# ISL91107.net
KiCad netlist of a schematic drawn in Altium Designer
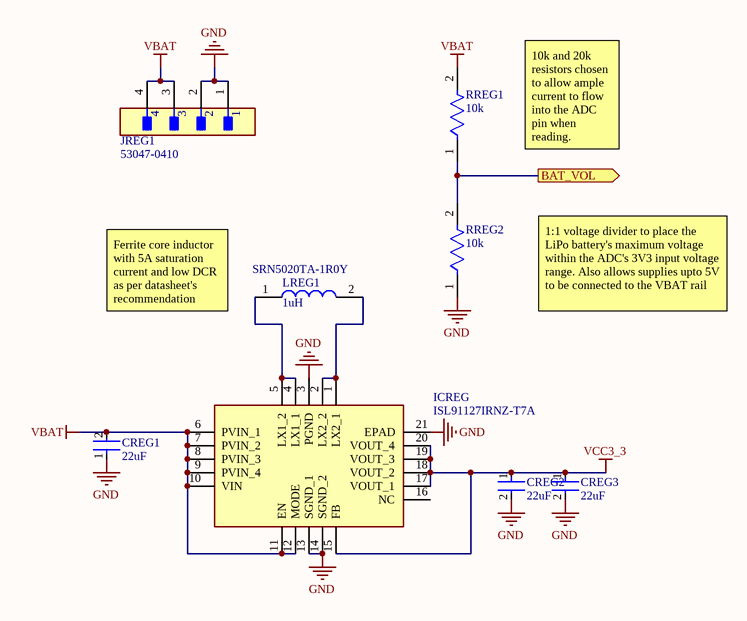
[diagram p0: ISL91107.SchDoc]

(export (version "E")
  (design (tool "Eeschema 10.0.6"))
  (components
    (comp (ref "CREG1")
      (value "22uF")
      (footprint "FP-GRM188-0_2-IPC_C")
      (description "Chip Multilayer Ceramic Capacitors for General Purpose, 0603, 22uF, X5R, 15%, 20%, 10V")
      (fields (field (name "TOLERANCE") "20%"))
      (libsource (lib "Altium Content Vault") (part "11868f565c42a9108669ba33697ecf6"))
    )
    (comp (ref "CREG2")
      (value "22uF")
      (footprint "FP-GRM188-0_2-IPC_C")
      (description "Chip Multilayer Ceramic Capacitors for General Purpose, 0603, 22uF, X5R, 15%, 20%, 10V")
      (fields (field (name "TOLERANCE") "20%"))
      (libsource (lib "Altium Content Vault") (part "11868f565c42a9108669ba33697ecf6"))
    )
    (comp (ref "CREG3")
      (value "22uF")
      (footprint "FP-GRM188-0_2-IPC_C")
      (description "Chip Multilayer Ceramic Capacitors for General Purpose, 0603, 22uF, X5R, 15%, 20%, 10V")
      (fields (field (name "TOLERANCE") "20%"))
      (libsource (lib "Altium Content Vault") (part "11868f565c42a9108669ba33697ecf6"))
    )
    (comp (ref "ICREG")
      (value "ISL91127IRNZ-T7A")
      (footprint "SamacSys:QFN50P400X400X100-21N")
      (description "Integrated Circuit")
      (fields (field (name "MOUSER PART NUMBER") "968-ISL91127IRNZ-T7A"))
      (libsource (lib "*") (part "ISL91127IRNZ-T7A"))
    )
    (comp (ref "JREG1")
      (value "53047-0410")
      (footprint "FP-53047-0410-MFG")
      (description "CONN HEADER VERT 4POS 1.25MM")
      (fields (field (name "VOLTAGE") "125V"))
      (libsource (lib "Altium Content Vault") (part "299a8cea1bdcbc3624fe62c390fa72c"))
    )
    (comp (ref "LREG1")
      (value "1uH")
      (footprint "SamacSys:INDC5050X200N")
      (description "Inductor")
      (fields
        (field (name "MANUFACTURER_PART_NUMBER") "SRN5020TA-1R0Y")
        (field (name "MOUSER PART NUMBER") "652-SRN5020TA-1R0Y")
        (field (name "SUPPLIER PART NUMBER 1") "SRN5020TA-1R0Y")
      )
      (libsource (lib "*") (part "SRN5020TA-1R0Y"))
    )
    (comp (ref "RREG1")
      (value "10k")
      (footprint "FP-ERJ3G-IPC_C")
      (description "RES SMD 10K OHM 5% 1/10W 0603")
      (fields (field (name "TOLERANCE") "5%"))
      (libsource (lib "Altium Content Vault") (part "1029c3af85768c4190bb7ad29bc67b5"))
    )
    (comp (ref "RREG2")
      (value "10k")
      (footprint "FP-ERJ3G-IPC_C")
      (description "RES SMD 10K OHM 5% 1/10W 0603")
      (fields (field (name "TOLERANCE") "5%"))
      (libsource (lib "Altium Content Vault") (part "1029c3af85768c4190bb7ad29bc67b5"))
    )
  )
  (nets
    (net (code "1") (name "/BAT_VOL") (class "Default")
      (node (ref "RREG1") (pin "1") (pinfunction "1_1") (pintype "passive"))
      (node (ref "RREG2") (pin "2") (pinfunction "2_2") (pintype "passive"))
    )
    (net (code "2") (name "GND") (class "Default")
      (node (ref "CREG1") (pin "1") (pinfunction "1_1") (pintype "passive"))
      (node (ref "CREG2") (pin "2") (pinfunction "2_2") (pintype "passive"))
      (node (ref "CREG3") (pin "2") (pinfunction "2_2") (pintype "passive"))
      (node (ref "ICREG") (pin "13") (pinfunction "SGND_1_13") (pintype "passive"))
      (node (ref "ICREG") (pin "14") (pinfunction "SGND_2_14") (pintype "passive"))
      (node (ref "ICREG") (pin "21") (pinfunction "EPAD_21") (pintype "passive"))
      (node (ref "ICREG") (pin "3") (pinfunction "PGND_3") (pintype "passive"))
      (node (ref "JREG1") (pin "1") (pinfunction "1_1") (pintype "passive"))
      (node (ref "JREG1") (pin "2") (pinfunction "2_2") (pintype "passive"))
      (node (ref "RREG2") (pin "1") (pinfunction "1_1") (pintype "passive"))
    )
    (net (code "3") (name "Net-(ICREG-LX1_1)") (class "Default")
      (node (ref "ICREG") (pin "4") (pinfunction "LX1_1_4") (pintype "passive"))
      (node (ref "ICREG") (pin "5") (pinfunction "LX1_2_5") (pintype "passive"))
      (node (ref "LREG1") (pin "1") (pinfunction "1_1") (pintype "passive"))
    )
    (net (code "4") (name "Net-(ICREG-LX2_1)") (class "Default")
      (node (ref "ICREG") (pin "1") (pinfunction "LX2_1_1") (pintype "passive"))
      (node (ref "ICREG") (pin "2") (pinfunction "LX2_2_2") (pintype "passive"))
      (node (ref "LREG1") (pin "2") (pinfunction "2_2") (pintype "passive"))
    )
    (net (code "5") (name "VBAT") (class "Default")
      (node (ref "CREG1") (pin "2") (pinfunction "2_2") (pintype "passive"))
      (node (ref "ICREG") (pin "10") (pinfunction "VIN_10") (pintype "passive"))
      (node (ref "ICREG") (pin "11") (pinfunction "EN_11") (pintype "passive"))
      (node (ref "ICREG") (pin "12") (pinfunction "MODE_12") (pintype "passive"))
      (node (ref "ICREG") (pin "6") (pinfunction "PVIN_1_6") (pintype "passive"))
      (node (ref "ICREG") (pin "7") (pinfunction "PVIN_2_7") (pintype "passive"))
      (node (ref "ICREG") (pin "8") (pinfunction "PVIN_3_8") (pintype "passive"))
      (node (ref "ICREG") (pin "9") (pinfunction "PVIN_4_9") (pintype "passive"))
      (node (ref "JREG1") (pin "3") (pinfunction "3_3") (pintype "passive"))
      (node (ref "JREG1") (pin "4") (pinfunction "4_4") (pintype "passive"))
      (node (ref "RREG1") (pin "2") (pinfunction "2_2") (pintype "passive"))
    )
    (net (code "6") (name "VCC3_3") (class "Default")
      (node (ref "CREG2") (pin "1") (pinfunction "1_1") (pintype "passive"))
      (node (ref "CREG3") (pin "1") (pinfunction "1_1") (pintype "passive"))
      (node (ref "ICREG") (pin "15") (pinfunction "FB_15") (pintype "passive"))
      (node (ref "ICREG") (pin "17") (pinfunction "VOUT_1_17") (pintype "passive"))
      (node (ref "ICREG") (pin "18") (pinfunction "VOUT_2_18") (pintype "passive"))
      (node (ref "ICREG") (pin "19") (pinfunction "VOUT_3_19") (pintype "passive"))
      (node (ref "ICREG") (pin "20") (pinfunction "VOUT_4_20") (pintype "passive"))
    )
    (net (code "7") (name "unconnected-(ICREG-NC-Pad16)") (class "Default")
      (node (ref "ICREG") (pin "16") (pinfunction "NC_16") (pintype "passive"))
    )
  )
)
